# CH340G_VCC.net
KiCad netlist of a schematic drawn in Altium Designer
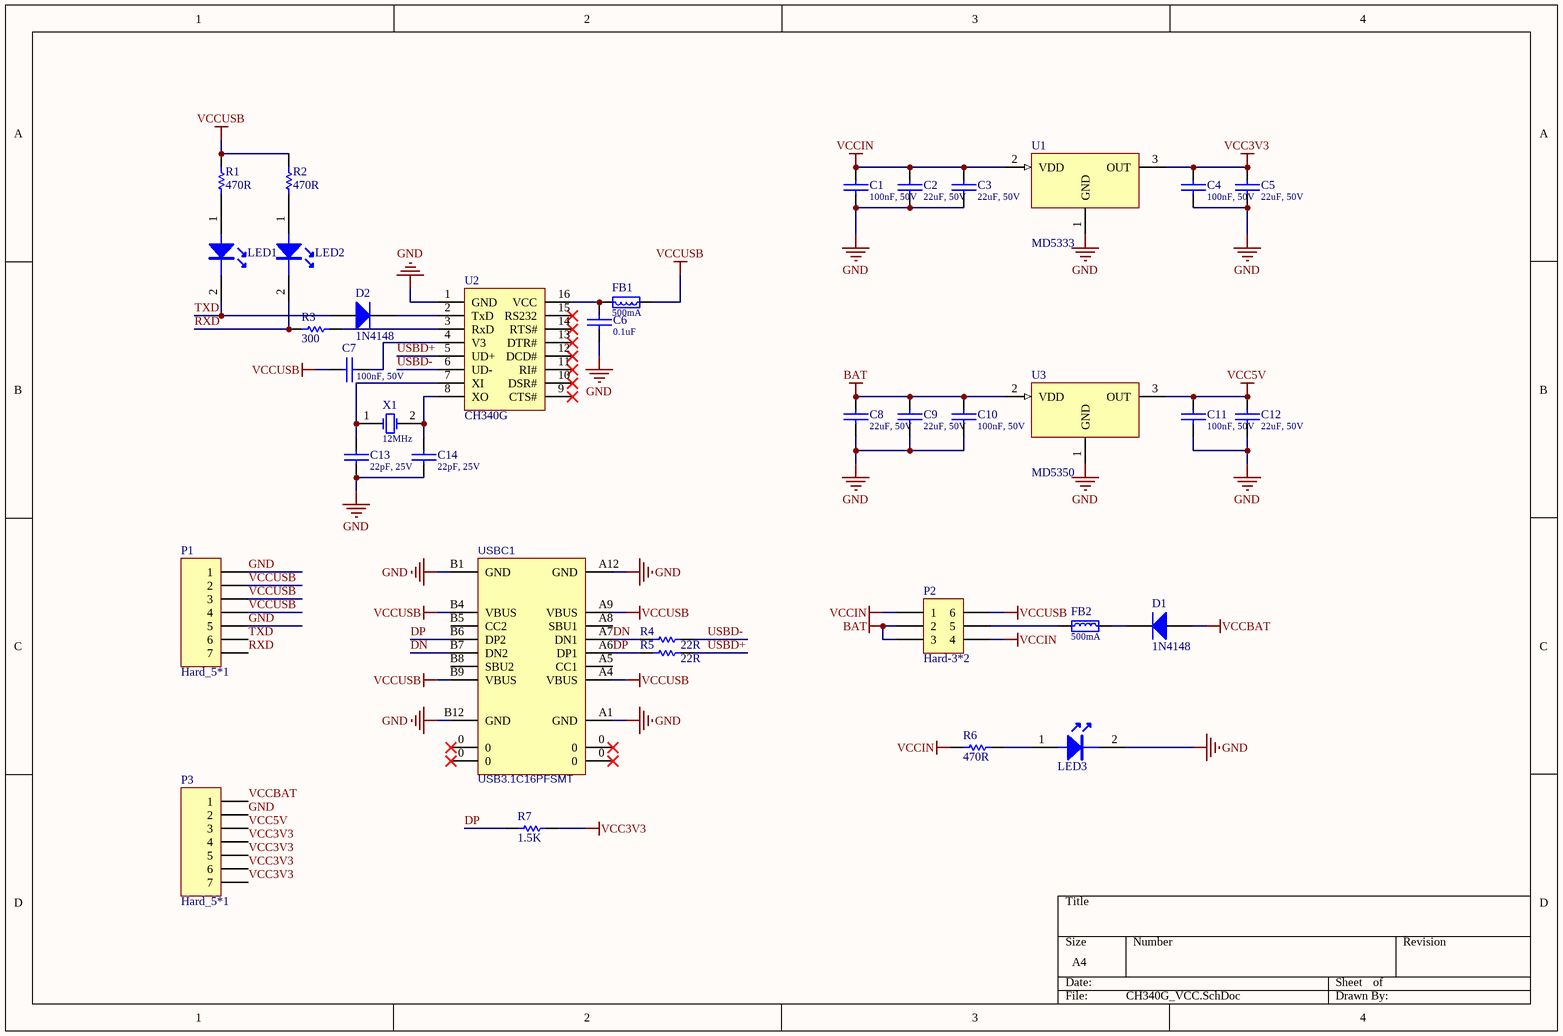
[diagram p0: CH340G_VCC.SchDoc]

(export (version "E")
  (design (tool "Eeschema 10.0.6"))
  (components
    (comp (ref "C1")
      (value "100nF, 50V")
      (footprint "C0603_QB")
      (description "Capacitor")
      (fields (field (name "MANUFACTURER") "国巨") (field (name "PARTNO") "11002050002"))
      (libsource (lib "Schlib1") (part "CAP"))
    )
    (comp (ref "C2")
      (value "22uF, 50V")
      (footprint "C0805_1.25mm_QB")
      (description "Capacitor")
      (fields (field (name "MANUFACTURER") "国巨") (field (name "PARTNO") "11002050002"))
      (libsource (lib "Schlib1") (part "CAP"))
    )
    (comp (ref "C3")
      (value "22uF, 50V")
      (footprint "C0805_1.25mm_QB")
      (description "Capacitor")
      (fields (field (name "MANUFACTURER") "国巨") (field (name "PARTNO") "11002050002"))
      (libsource (lib "Schlib1") (part "CAP"))
    )
    (comp (ref "C4")
      (value "100nF, 50V")
      (footprint "C0603_QB")
      (description "Capacitor")
      (fields (field (name "MANUFACTURER") "国巨") (field (name "PARTNO") "11002050002"))
      (libsource (lib "Schlib1") (part "CAP"))
    )
    (comp (ref "C5")
      (value "22uF, 50V")
      (footprint "C0805_1.25mm_QB")
      (description "Capacitor")
      (fields (field (name "MANUFACTURER") "国巨") (field (name "PARTNO") "11002050002"))
      (libsource (lib "Schlib1") (part "CAP"))
    )
    (comp (ref "C6")
      (value "0.1uF")
      (footprint "C0603_QB")
      (description "Capacitor")
      (fields (field (name "MANUFACTURER") "国巨") (field (name "PARTNO") "11002050002"))
      (libsource (lib "Schlib1") (part "CAP"))
    )
    (comp (ref "C7")
      (value "100nF, 50V")
      (footprint "C0603_QB")
      (description "Capacitor")
      (fields (field (name "MANUFACTURER") "国巨") (field (name "PARTNO") "11002050002"))
      (libsource (lib "Schlib1") (part "CAP"))
    )
    (comp (ref "C8")
      (value "22uF, 50V")
      (footprint "C0805_1.25mm_QB")
      (description "Capacitor")
      (fields (field (name "MANUFACTURER") "国巨") (field (name "PARTNO") "11002050002"))
      (libsource (lib "Schlib1") (part "CAP"))
    )
    (comp (ref "C9")
      (value "22uF, 50V")
      (footprint "C0805_1.25mm_QB")
      (description "Capacitor")
      (fields (field (name "MANUFACTURER") "国巨") (field (name "PARTNO") "11002050002"))
      (libsource (lib "Schlib1") (part "CAP"))
    )
    (comp (ref "C10")
      (value "100nF, 50V")
      (footprint "C0603_QB")
      (description "Capacitor")
      (fields (field (name "MANUFACTURER") "国巨") (field (name "PARTNO") "11002050002"))
      (libsource (lib "Schlib1") (part "CAP"))
    )
    (comp (ref "C11")
      (value "100nF, 50V")
      (footprint "C0603_QB")
      (description "Capacitor")
      (fields (field (name "MANUFACTURER") "国巨") (field (name "PARTNO") "11002050002"))
      (libsource (lib "Schlib1") (part "CAP"))
    )
    (comp (ref "C12")
      (value "22uF, 50V")
      (footprint "C0805_1.25mm_QB")
      (description "Capacitor")
      (fields (field (name "MANUFACTURER") "国巨") (field (name "PARTNO") "11002050002"))
      (libsource (lib "Schlib1") (part "CAP"))
    )
    (comp (ref "C13")
      (value "22pF, 25V")
      (footprint "C0603_QB")
      (description "Capacitor")
      (fields (field (name "MANUFACTURER") "国巨") (field (name "PARTNO") "11002050002"))
      (libsource (lib "Schlib1") (part "CAP"))
    )
    (comp (ref "C14")
      (value "22pF, 25V")
      (footprint "C0603_QB")
      (description "Capacitor")
      (fields (field (name "MANUFACTURER") "国巨") (field (name "PARTNO") "11002050002"))
      (libsource (lib "Schlib1") (part "CAP"))
    )
    (comp (ref "D1") (value "1N4148") (footprint "SOD_523_QB") (libsource (lib "Schlib1") (part "diode")))
    (comp (ref "D2") (value "1N4148") (footprint "SOD_523_QB") (libsource (lib "Schlib1") (part "diode")))
    (comp (ref "FB1")
      (value "500mA")
      (footprint "FB0603_QB")
      (description "Inductor")
      (fields (field (name "MANUFACTURER") "HOLDER") (field (name "Comment") "CBG160808U182"))
      (libsource (lib "Schlib1") (part "FB"))
    )
    (comp (ref "FB2")
      (value "500mA")
      (footprint "FB0603_QB")
      (description "Inductor")
      (fields (field (name "MANUFACTURER") "HOLDER") (field (name "Comment") "CBG160808U182"))
      (libsource (lib "Schlib1") (part "FB"))
    )
    (comp (ref "LED1")
      (value "19-217/R6C-AL1M2VY/3T")
      (footprint "LED_SMT_QB")
      (fields (field (name "MANUFACTURER") "亿光") (field (name "PARTNO") "11004030004"))
      (libsource (lib "Schlib1") (part "LED"))
    )
    (comp (ref "LED2")
      (value "19-217/R6C-AL1M2VY/3T")
      (footprint "LED_SMT_QB")
      (fields (field (name "MANUFACTURER") "亿光") (field (name "PARTNO") "11004030004"))
      (libsource (lib "Schlib1") (part "LED"))
    )
    (comp (ref "LED3")
      (value "19-217/R6C-AL1M2VY/3T")
      (footprint "LED_SMT_QB")
      (fields (field (name "MANUFACTURER") "亿光") (field (name "PARTNO") "11004030004"))
      (libsource (lib "Schlib1") (part "LED"))
    )
    (comp (ref "P1")
      (value "Hard_5*1")
      (footprint "HDR2.54-LI-4P")
      (libsource (lib "CH340G_VCC") (part "Hard_5*1"))
    )
    (comp (ref "P2")
      (value "Hard-3*2")
      (footprint "HDR2.54-LI-2x3P")
      (libsource (lib "Schlib1") (part "Hard-3*2"))
    )
    (comp (ref "P3")
      (value "Hard_5*1")
      (footprint "HDR2.54-LI-4P")
      (libsource (lib "CH340G_VCC") (part "Hard_5*1"))
    )
    (comp (ref "R1")
      (value "470R")
      (footprint "R0603_QB")
      (description "Resistor")
      (fields (field (name "MANUFACTURER") "国巨") (field (name "PARTNO") "11003020066"))
      (libsource (lib "Schlib1") (part "Res1"))
    )
    (comp (ref "R2")
      (value "470R")
      (footprint "R0603_QB")
      (description "Resistor")
      (fields (field (name "MANUFACTURER") "国巨") (field (name "PARTNO") "11003020066"))
      (libsource (lib "Schlib1") (part "Res1"))
    )
    (comp (ref "R3")
      (value "300")
      (footprint "R0603_QB")
      (description "Resistor")
      (fields (field (name "MANUFACTURER") "国巨") (field (name "PARTNO") "11003020066"))
      (libsource (lib "Schlib1") (part "Res1"))
    )
    (comp (ref "R4")
      (value "22R")
      (footprint "C0603_QB")
      (description "Resistor")
      (fields (field (name "MANUFACTURER") "国巨") (field (name "PARTNO") "11003020066"))
      (libsource (lib "Schlib1") (part "Res1"))
    )
    (comp (ref "R5")
      (value "22R")
      (footprint "C0603_QB")
      (description "Resistor")
      (fields (field (name "MANUFACTURER") "国巨") (field (name "PARTNO") "11003020066"))
      (libsource (lib "Schlib1") (part "Res1"))
    )
    (comp (ref "R6")
      (value "470R")
      (footprint "R0603_QB")
      (description "Resistor")
      (fields (field (name "MANUFACTURER") "国巨") (field (name "PARTNO") "11003020066"))
      (libsource (lib "Schlib1") (part "Res1"))
    )
    (comp (ref "R7")
      (value "1.5K")
      (footprint "R0603_QB")
      (description "Resistor")
      (fields (field (name "MANUFACTURER") "国巨") (field (name "PARTNO") "11003020066"))
      (libsource (lib "Schlib1") (part "Res1"))
    )
    (comp (ref "U1")
      (value "MD5333")
      (footprint "SOT_89_QB")
      (description "LDO")
      (fields (field (name "MANUFACTURER") "明达微") (field (name "PARTNO") "11001090038"))
      (libsource (lib "Schlib1") (part "MD5333"))
    )
    (comp (ref "U2") (value "CH340G") (footprint "SOP16N_N") (libsource (lib "Schlib1") (part "CH340G")))
    (comp (ref "U3")
      (value "MD5350")
      (footprint "SOT_89_QB")
      (description "LDO")
      (fields (field (name "MANUFACTURER") "明达微") (field (name "PARTNO") "11001090038"))
      (libsource (lib "Schlib1") (part "MD5350"))
    )
    (comp (ref "USBC1")
      (value "USB3.1C16PFSMT")
      (footprint "TYPE-C-USB-17")
      (libsource (lib "Schlib1") (part "USB3.1C16PFSMT"))
    )
    (comp (ref "X1")
      (value "12MHz")
      (footprint "ESB3.68640F20M23_QB")
      (description "Crystal Oscillator")
      (fields (field (name "MANUFACTURER") "EPSON") (field (name "PARTNO") "11012040004"))
      (libsource (lib "Schlib1") (part "XTAL"))
    )
  )
  (nets
    (net (code "1") (name "/DN") (class "Default")
      (node (ref "R4") (pin "1") (pinfunction "1_1") (pintype "passive"))
      (node (ref "USBC1") (pin "A7") (pinfunction "DN1_A7") (pintype "passive"))
      (node (ref "USBC1") (pin "B7") (pinfunction "DN2_B7") (pintype "passive"))
    )
    (net (code "2") (name "/DP") (class "Default")
      (node (ref "R5") (pin "1") (pinfunction "1_1") (pintype "passive"))
      (node (ref "R7") (pin "1") (pinfunction "1_1") (pintype "passive"))
      (node (ref "USBC1") (pin "A6") (pinfunction "DP1_A6") (pintype "passive"))
      (node (ref "USBC1") (pin "B6") (pinfunction "DP2_B6") (pintype "passive"))
    )
    (net (code "3") (name "/RXD") (class "Default")
      (node (ref "LED2") (pin "2") (pinfunction "K_2") (pintype "passive"))
      (node (ref "P1") (pin "7") (pinfunction "7_7") (pintype "passive"))
      (node (ref "R3") (pin "1") (pinfunction "1_1") (pintype "passive"))
    )
    (net (code "4") (name "/TXD") (class "Default")
      (node (ref "D2") (pin "1") (pinfunction "A_1") (pintype "passive"))
      (node (ref "LED1") (pin "2") (pinfunction "K_2") (pintype "passive"))
      (node (ref "P1") (pin "6") (pinfunction "6_6") (pintype "passive"))
    )
    (net (code "5") (name "/USBD+") (class "Default")
      (node (ref "R5") (pin "2") (pinfunction "2_2") (pintype "passive"))
      (node (ref "U2") (pin "5") (pinfunction "UD+_5") (pintype "passive"))
    )
    (net (code "6") (name "/USBD-") (class "Default")
      (node (ref "R4") (pin "2") (pinfunction "2_2") (pintype "passive"))
      (node (ref "U2") (pin "6") (pinfunction "UD-_6") (pintype "passive"))
    )
    (net (code "7") (name "BAT") (class "Default")
      (node (ref "C10") (pin "2") (pinfunction "2_2") (pintype "passive"))
      (node (ref "C8") (pin "2") (pinfunction "2_2") (pintype "passive"))
      (node (ref "C9") (pin "2") (pinfunction "2_2") (pintype "passive"))
      (node (ref "P2") (pin "2") (pinfunction "2_2") (pintype "passive"))
      (node (ref "P2") (pin "3") (pinfunction "3_3") (pintype "passive"))
      (node (ref "U3") (pin "2") (pinfunction "VDD_2") (pintype "input"))
    )
    (net (code "8") (name "GND") (class "Default")
      (node (ref "C1") (pin "1") (pinfunction "1_1") (pintype "passive"))
      (node (ref "C10") (pin "1") (pinfunction "1_1") (pintype "passive"))
      (node (ref "C11") (pin "1") (pinfunction "1_1") (pintype "passive"))
      (node (ref "C12") (pin "1") (pinfunction "1_1") (pintype "passive"))
      (node (ref "C13") (pin "1") (pinfunction "1_1") (pintype "passive"))
      (node (ref "C14") (pin "1") (pinfunction "1_1") (pintype "passive"))
      (node (ref "C2") (pin "1") (pinfunction "1_1") (pintype "passive"))
      (node (ref "C3") (pin "1") (pinfunction "1_1") (pintype "passive"))
      (node (ref "C4") (pin "1") (pinfunction "1_1") (pintype "passive"))
      (node (ref "C5") (pin "1") (pinfunction "1_1") (pintype "passive"))
      (node (ref "C6") (pin "1") (pinfunction "1_1") (pintype "passive"))
      (node (ref "C8") (pin "1") (pinfunction "1_1") (pintype "passive"))
      (node (ref "C9") (pin "1") (pinfunction "1_1") (pintype "passive"))
      (node (ref "LED3") (pin "2") (pinfunction "K_2") (pintype "passive"))
      (node (ref "P1") (pin "1") (pinfunction "1_1") (pintype "passive"))
      (node (ref "P1") (pin "5") (pinfunction "5_5") (pintype "passive"))
      (node (ref "P3") (pin "2") (pinfunction "2_2") (pintype "passive"))
      (node (ref "U1") (pin "1") (pinfunction "GND_1") (pintype "passive"))
      (node (ref "U2") (pin "1") (pinfunction "GND_1") (pintype "passive"))
      (node (ref "U3") (pin "1") (pinfunction "GND_1") (pintype "passive"))
      (node (ref "USBC1") (pin "A1") (pinfunction "GND_A1") (pintype "passive"))
      (node (ref "USBC1") (pin "A12") (pinfunction "GND_A12") (pintype "passive"))
      (node (ref "USBC1") (pin "B1") (pinfunction "GND_B1") (pintype "passive"))
      (node (ref "USBC1") (pin "B12") (pinfunction "GND_B12") (pintype "passive"))
    )
    (net (code "9") (name "Net-(D1-K)") (class "Default")
      (node (ref "D1") (pin "2") (pinfunction "K_2") (pintype "passive"))
      (node (ref "FB2") (pin "2") (pinfunction "2_2") (pintype "passive"))
    )
    (net (code "10") (name "Net-(D2-K)") (class "Default")
      (node (ref "D2") (pin "2") (pinfunction "K_2") (pintype "passive"))
      (node (ref "U2") (pin "2") (pinfunction "TxD_2") (pintype "passive"))
    )
    (net (code "11") (name "Net-(FB2-Pad1)") (class "Default")
      (node (ref "FB2") (pin "1") (pinfunction "1_1") (pintype "passive"))
      (node (ref "P2") (pin "5") (pinfunction "5_5") (pintype "passive"))
    )
    (net (code "12") (name "Net-(LED1-A)") (class "Default")
      (node (ref "LED1") (pin "1") (pinfunction "A_1") (pintype "passive"))
      (node (ref "R1") (pin "1") (pinfunction "1_1") (pintype "passive"))
    )
    (net (code "13") (name "Net-(LED2-A)") (class "Default")
      (node (ref "LED2") (pin "1") (pinfunction "A_1") (pintype "passive"))
      (node (ref "R2") (pin "1") (pinfunction "1_1") (pintype "passive"))
    )
    (net (code "14") (name "Net-(LED3-A)") (class "Default")
      (node (ref "LED3") (pin "1") (pinfunction "A_1") (pintype "passive"))
      (node (ref "R6") (pin "2") (pinfunction "2_2") (pintype "passive"))
    )
    (net (code "15") (name "Net-(U2-RxD)") (class "Default")
      (node (ref "R3") (pin "2") (pinfunction "2_2") (pintype "passive"))
      (node (ref "U2") (pin "3") (pinfunction "RxD_3") (pintype "passive"))
    )
    (net (code "16") (name "Net-(U2-V3)") (class "Default")
      (node (ref "C7") (pin "2") (pinfunction "2_2") (pintype "passive"))
      (node (ref "U2") (pin "4") (pinfunction "V3_4") (pintype "passive"))
    )
    (net (code "17") (name "Net-(U2-VCC)") (class "Default")
      (node (ref "C6") (pin "2") (pinfunction "2_2") (pintype "passive"))
      (node (ref "FB1") (pin "2") (pinfunction "2_2") (pintype "passive"))
      (node (ref "U2") (pin "16") (pinfunction "VCC_16") (pintype "passive"))
    )
    (net (code "18") (name "Net-(U2-XI)") (class "Default")
      (node (ref "C13") (pin "2") (pinfunction "2_2") (pintype "passive"))
      (node (ref "U2") (pin "7") (pinfunction "XI_7") (pintype "passive"))
      (node (ref "X1") (pin "1") (pinfunction "OSC1_1") (pintype "passive"))
    )
    (net (code "19") (name "Net-(U2-XO)") (class "Default")
      (node (ref "C14") (pin "2") (pinfunction "2_2") (pintype "passive"))
      (node (ref "U2") (pin "8") (pinfunction "XO_8") (pintype "passive"))
      (node (ref "X1") (pin "2") (pinfunction "OSC2_2") (pintype "passive"))
    )
    (net (code "20") (name "VCC3V3") (class "Default")
      (node (ref "C4") (pin "2") (pinfunction "2_2") (pintype "passive"))
      (node (ref "C5") (pin "2") (pinfunction "2_2") (pintype "passive"))
      (node (ref "P3") (pin "4") (pinfunction "4_4") (pintype "passive"))
      (node (ref "P3") (pin "5") (pinfunction "5_5") (pintype "passive"))
      (node (ref "P3") (pin "6") (pinfunction "6_6") (pintype "passive"))
      (node (ref "P3") (pin "7") (pinfunction "7_7") (pintype "passive"))
      (node (ref "R7") (pin "2") (pinfunction "2_2") (pintype "passive"))
      (node (ref "U1") (pin "3") (pinfunction "OUT_3") (pintype "power_in"))
    )
    (net (code "21") (name "VCC5V") (class "Default")
      (node (ref "C11") (pin "2") (pinfunction "2_2") (pintype "passive"))
      (node (ref "C12") (pin "2") (pinfunction "2_2") (pintype "passive"))
      (node (ref "P3") (pin "3") (pinfunction "3_3") (pintype "passive"))
      (node (ref "U3") (pin "3") (pinfunction "OUT_3") (pintype "power_in"))
    )
    (net (code "22") (name "VCCBAT") (class "Default")
      (node (ref "D1") (pin "1") (pinfunction "A_1") (pintype "passive"))
      (node (ref "P3") (pin "1") (pinfunction "1_1") (pintype "passive"))
    )
    (net (code "23") (name "VCCIN") (class "Default")
      (node (ref "C1") (pin "2") (pinfunction "2_2") (pintype "passive"))
      (node (ref "C2") (pin "2") (pinfunction "2_2") (pintype "passive"))
      (node (ref "C3") (pin "2") (pinfunction "2_2") (pintype "passive"))
      (node (ref "P2") (pin "1") (pinfunction "1_1") (pintype "passive"))
      (node (ref "P2") (pin "4") (pinfunction "4_4") (pintype "passive"))
      (node (ref "R6") (pin "1") (pinfunction "1_1") (pintype "passive"))
      (node (ref "U1") (pin "2") (pinfunction "VDD_2") (pintype "input"))
    )
    (net (code "24") (name "VCCUSB") (class "Default")
      (node (ref "C7") (pin "1") (pinfunction "1_1") (pintype "passive"))
      (node (ref "FB1") (pin "1") (pinfunction "1_1") (pintype "passive"))
      (node (ref "P1") (pin "2") (pinfunction "2_2") (pintype "passive"))
      (node (ref "P1") (pin "3") (pinfunction "3_3") (pintype "passive"))
      (node (ref "P1") (pin "4") (pinfunction "4_4") (pintype "passive"))
      (node (ref "P2") (pin "6") (pinfunction "6_6") (pintype "passive"))
      (node (ref "R1") (pin "2") (pinfunction "2_2") (pintype "passive"))
      (node (ref "R2") (pin "2") (pinfunction "2_2") (pintype "passive"))
      (node (ref "USBC1") (pin "A4") (pinfunction "VBUS_A4") (pintype "passive"))
      (node (ref "USBC1") (pin "A9") (pinfunction "VBUS_A9") (pintype "passive"))
      (node (ref "USBC1") (pin "B4") (pinfunction "VBUS_B4") (pintype "passive"))
      (node (ref "USBC1") (pin "B9") (pinfunction "VBUS_B9") (pintype "passive"))
    )
    (net (code "25") (name "unconnected-(U2-CTS#-Pad9)") (class "Default")
      (node (ref "U2") (pin "9") (pinfunction "CTS#_9") (pintype "passive+no_connect"))
    )
    (net (code "26") (name "unconnected-(U2-DCD#-Pad12)") (class "Default")
      (node (ref "U2") (pin "12") (pinfunction "DCD#_12") (pintype "passive+no_connect"))
    )
    (net (code "27") (name "unconnected-(U2-DSR#-Pad10)") (class "Default")
      (node (ref "U2") (pin "10") (pinfunction "DSR#_10") (pintype "passive+no_connect"))
    )
    (net (code "28") (name "unconnected-(U2-DTR#-Pad13)") (class "Default")
      (node (ref "U2") (pin "13") (pinfunction "DTR#_13") (pintype "passive+no_connect"))
    )
    (net (code "29") (name "unconnected-(U2-RI#-Pad11)") (class "Default")
      (node (ref "U2") (pin "11") (pinfunction "RI#_11") (pintype "passive+no_connect"))
    )
    (net (code "30") (name "unconnected-(U2-RS232-Pad15)") (class "Default")
      (node (ref "U2") (pin "15") (pinfunction "RS232_15") (pintype "passive+no_connect"))
    )
    (net (code "31") (name "unconnected-(U2-RTS#-Pad14)") (class "Default")
      (node (ref "U2") (pin "14") (pinfunction "RTS#_14") (pintype "passive+no_connect"))
    )
    (net (code "32") (name "unconnected-(USBC1-CC1-PadA5)") (class "Default")
      (node (ref "USBC1") (pin "A5") (pinfunction "CC1_A5") (pintype "passive"))
    )
    (net (code "33") (name "unconnected-(USBC1-CC2-PadB5)") (class "Default")
      (node (ref "USBC1") (pin "B5") (pinfunction "CC2_B5") (pintype "passive"))
    )
    (net (code "34") (name "unconnected-(USBC1-Pad0)") (class "Default")
      (node (ref "USBC1") (pin "0") (pinfunction "0_0") (pintype "passive+no_connect"))
    )
    (net (code "35") (name "unconnected-(USBC1-Pad0)_1") (class "Default")
      (node (ref "USBC1") (pin "0") (pinfunction "0_0") (pintype "passive+no_connect"))
    )
    (net (code "36") (name "unconnected-(USBC1-Pad0)_2") (class "Default")
      (node (ref "USBC1") (pin "0") (pinfunction "0_0") (pintype "passive+no_connect"))
    )
    (net (code "37") (name "unconnected-(USBC1-Pad0)_3") (class "Default")
      (node (ref "USBC1") (pin "0") (pinfunction "0_0") (pintype "passive+no_connect"))
    )
    (net (code "38") (name "unconnected-(USBC1-SBU1-PadA8)") (class "Default")
      (node (ref "USBC1") (pin "A8") (pinfunction "SBU1_A8") (pintype "passive"))
    )
    (net (code "39") (name "unconnected-(USBC1-SBU2-PadB8)") (class "Default")
      (node (ref "USBC1") (pin "B8") (pinfunction "SBU2_B8") (pintype "passive"))
    )
  )
)
